# untitled.net
KiCad netlist of a schematic drawn in EAGLE
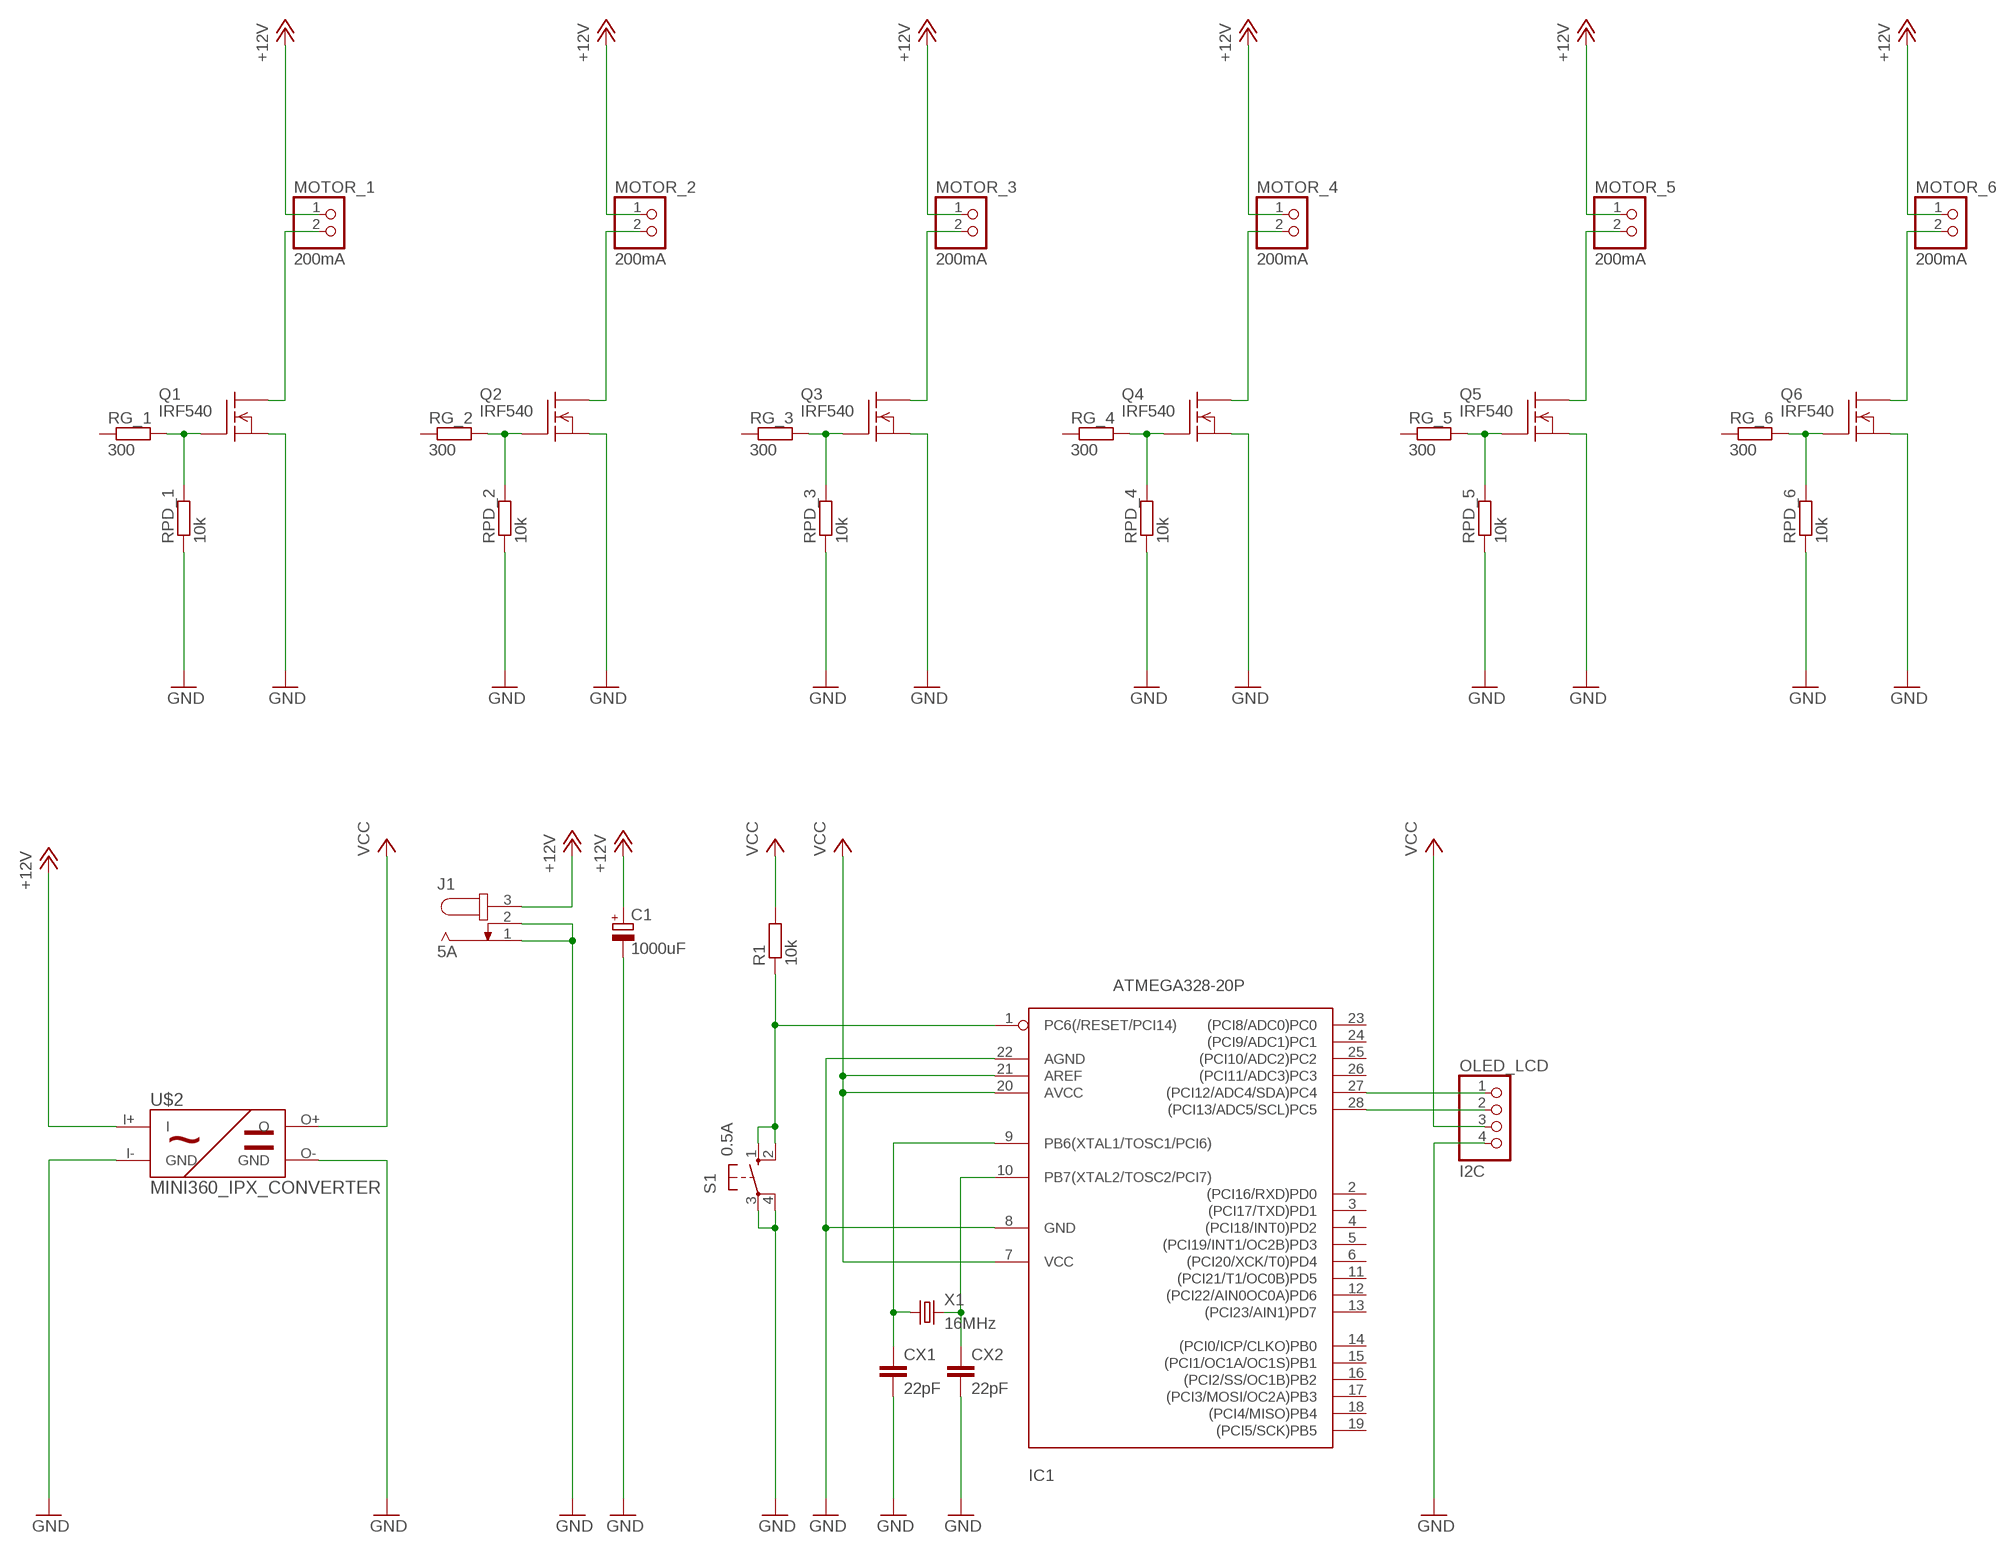
[diagram p0: schematic, sheet 1]

(export (version "E")
  (design (tool "Eeschema 10.0.6"))
  (components
    (comp (ref "C1")
      (value "1000uF")
      (footprint "eagle-import:E5-8,5")
      (libsource (lib "eagle-import") (part "CPOL-EUE5-8.5"))
    )
    (comp (ref "CX1")
      (value "22pF")
      (footprint "eagle-import:C050-025X075")
      (libsource (lib "eagle-import") (part "C-EU050-025X075"))
    )
    (comp (ref "CX2")
      (value "22pF")
      (footprint "eagle-import:C050-025X075")
      (libsource (lib "eagle-import") (part "C-EU050-025X075"))
    )
    (comp (ref "IC1")
      (value "ATMEGA328-20P")
      (footprint "eagle-import:DIL28-3")
      (libsource (lib "eagle-import") (part "ATMEGA328P-20"))
    )
    (comp (ref "J1")
      (value "5A")
      (footprint "eagle-import:SPC4078")
      (libsource (lib "eagle-import") (part "JACK-PLUG1"))
    )
    (comp (ref "MOTOR_1")
      (value "200mA")
      (footprint "eagle-import:1X02")
      (libsource (lib "eagle-import") (part "PINHD-1X2"))
    )
    (comp (ref "MOTOR_2")
      (value "200mA")
      (footprint "eagle-import:1X02")
      (libsource (lib "eagle-import") (part "PINHD-1X2"))
    )
    (comp (ref "MOTOR_3")
      (value "200mA")
      (footprint "eagle-import:1X02")
      (libsource (lib "eagle-import") (part "PINHD-1X2"))
    )
    (comp (ref "MOTOR_4")
      (value "200mA")
      (footprint "eagle-import:1X02")
      (libsource (lib "eagle-import") (part "PINHD-1X2"))
    )
    (comp (ref "MOTOR_5")
      (value "200mA")
      (footprint "eagle-import:1X02")
      (libsource (lib "eagle-import") (part "PINHD-1X2"))
    )
    (comp (ref "MOTOR_6")
      (value "200mA")
      (footprint "eagle-import:1X02")
      (libsource (lib "eagle-import") (part "PINHD-1X2"))
    )
    (comp (ref "OLED_LCD")
      (value "I2C")
      (footprint "eagle-import:1X04")
      (libsource (lib "eagle-import") (part "PINHD-1X4"))
    )
    (comp (ref "Q1")
      (value "IRF540")
      (footprint "eagle-import:TO220")
      (libsource (lib "eagle-import") (part "IRF540"))
    )
    (comp (ref "Q2")
      (value "IRF540")
      (footprint "eagle-import:TO220")
      (libsource (lib "eagle-import") (part "IRF540"))
    )
    (comp (ref "Q3")
      (value "IRF540")
      (footprint "eagle-import:TO220")
      (libsource (lib "eagle-import") (part "IRF540"))
    )
    (comp (ref "Q4")
      (value "IRF540")
      (footprint "eagle-import:TO220")
      (libsource (lib "eagle-import") (part "IRF540"))
    )
    (comp (ref "Q5")
      (value "IRF540")
      (footprint "eagle-import:TO220")
      (libsource (lib "eagle-import") (part "IRF540"))
    )
    (comp (ref "Q6")
      (value "IRF540")
      (footprint "eagle-import:TO220")
      (libsource (lib "eagle-import") (part "IRF540"))
    )
    (comp (ref "R1")
      (value "10k")
      (footprint "eagle-import:0207_10")
      (libsource (lib "eagle-import") (part "R-EU_0207/10"))
    )
    (comp (ref "RG_1")
      (value "300")
      (footprint "eagle-import:0207_10")
      (libsource (lib "eagle-import") (part "R-EU_0207/10"))
    )
    (comp (ref "RG_2")
      (value "300")
      (footprint "eagle-import:0207_10")
      (libsource (lib "eagle-import") (part "R-EU_0207/10"))
    )
    (comp (ref "RG_3")
      (value "300")
      (footprint "eagle-import:0207_10")
      (libsource (lib "eagle-import") (part "R-EU_0207/10"))
    )
    (comp (ref "RG_4")
      (value "300")
      (footprint "eagle-import:0207_10")
      (libsource (lib "eagle-import") (part "R-EU_0207/10"))
    )
    (comp (ref "RG_5")
      (value "300")
      (footprint "eagle-import:0207_10")
      (libsource (lib "eagle-import") (part "R-EU_0207/10"))
    )
    (comp (ref "RG_6")
      (value "300")
      (footprint "eagle-import:0207_10")
      (libsource (lib "eagle-import") (part "R-EU_0207/10"))
    )
    (comp (ref "RPD_1")
      (value "10k")
      (footprint "eagle-import:0207_10")
      (libsource (lib "eagle-import") (part "R-EU_0207/10"))
    )
    (comp (ref "RPD_2")
      (value "10k")
      (footprint "eagle-import:0207_10")
      (libsource (lib "eagle-import") (part "R-EU_0207/10"))
    )
    (comp (ref "RPD_3")
      (value "10k")
      (footprint "eagle-import:0207_10")
      (libsource (lib "eagle-import") (part "R-EU_0207/10"))
    )
    (comp (ref "RPD_4")
      (value "10k")
      (footprint "eagle-import:0207_10")
      (libsource (lib "eagle-import") (part "R-EU_0207/10"))
    )
    (comp (ref "RPD_5")
      (value "10k")
      (footprint "eagle-import:0207_10")
      (libsource (lib "eagle-import") (part "R-EU_0207/10"))
    )
    (comp (ref "RPD_6")
      (value "10k")
      (footprint "eagle-import:0207_10")
      (libsource (lib "eagle-import") (part "R-EU_0207/10"))
    )
    (comp (ref "S1")
      (value "0.5A")
      (footprint "eagle-import:B3F-10XX")
      (fields (field (name "MPN") "B3F-1000"))
      (libsource (lib "eagle-import") (part "10-XX"))
    )
    (comp (ref "U$2")
      (value "MINI360_IPX_CONVERTER")
      (footprint "eagle-import:MINI360_IPX_CONVERTER")
      (libsource (lib "eagle-import") (part "MINI360_IPX_CONVERTER"))
    )
    (comp (ref "X1")
      (value "16MHz")
      (footprint "eagle-import:HC49_S")
      (libsource (lib "eagle-import") (part "CRYSTALHC49S"))
    )
  )
  (nets
    (net (code "1") (name "+12V") (class "Default")
      (node (ref "C1") (pin "+") (pinfunction "+_+") (pintype "passive"))
      (node (ref "J1") (pin "3") (pinfunction "3_3") (pintype "passive"))
      (node (ref "MOTOR_1") (pin "1") (pinfunction "1_1") (pintype "passive"))
      (node (ref "MOTOR_2") (pin "1") (pinfunction "1_1") (pintype "passive"))
      (node (ref "MOTOR_3") (pin "1") (pinfunction "1_1") (pintype "passive"))
      (node (ref "MOTOR_4") (pin "1") (pinfunction "1_1") (pintype "passive"))
      (node (ref "MOTOR_5") (pin "1") (pinfunction "1_1") (pintype "passive"))
      (node (ref "MOTOR_6") (pin "1") (pinfunction "1_1") (pintype "passive"))
      (node (ref "U$2") (pin "I+") (pinfunction "I_I+") (pintype "bidirectional"))
    )
    (net (code "2") (name "GND") (class "Default")
      (node (ref "C1") (pin "-") (pinfunction "-_-") (pintype "passive"))
      (node (ref "CX1") (pin "2") (pinfunction "2_2") (pintype "passive"))
      (node (ref "CX2") (pin "2") (pinfunction "2_2") (pintype "passive"))
      (node (ref "IC1") (pin "22") (pinfunction "AGND_22") (pintype "bidirectional"))
      (node (ref "IC1") (pin "8") (pinfunction "GND_8") (pintype "bidirectional"))
      (node (ref "J1") (pin "1") (pinfunction "1_1") (pintype "passive"))
      (node (ref "J1") (pin "2") (pinfunction "2_2") (pintype "passive"))
      (node (ref "OLED_LCD") (pin "4") (pinfunction "4_4") (pintype "passive"))
      (node (ref "Q1") (pin "3") (pinfunction "S_3") (pintype "passive"))
      (node (ref "Q2") (pin "3") (pinfunction "S_3") (pintype "passive"))
      (node (ref "Q3") (pin "3") (pinfunction "S_3") (pintype "passive"))
      (node (ref "Q4") (pin "3") (pinfunction "S_3") (pintype "passive"))
      (node (ref "Q5") (pin "3") (pinfunction "S_3") (pintype "passive"))
      (node (ref "Q6") (pin "3") (pinfunction "S_3") (pintype "passive"))
      (node (ref "RPD_1") (pin "1") (pinfunction "1_1") (pintype "passive"))
      (node (ref "RPD_2") (pin "1") (pinfunction "1_1") (pintype "passive"))
      (node (ref "RPD_3") (pin "1") (pinfunction "1_1") (pintype "passive"))
      (node (ref "RPD_4") (pin "1") (pinfunction "1_1") (pintype "passive"))
      (node (ref "RPD_5") (pin "1") (pinfunction "1_1") (pintype "passive"))
      (node (ref "RPD_6") (pin "1") (pinfunction "1_1") (pintype "passive"))
      (node (ref "S1") (pin "3") (pinfunction "P_3") (pintype "passive"))
      (node (ref "S1") (pin "4") (pinfunction "P1_4") (pintype "passive"))
      (node (ref "U$2") (pin "I-") (pinfunction "GND_I-") (pintype "bidirectional"))
      (node (ref "U$2") (pin "O-") (pinfunction "GND_O-") (pintype "bidirectional"))
    )
    (net (code "3") (name "Net-(IC1-(PCI12{slash}ADC4{slash}SDA)PC4)") (class "Default")
      (node (ref "IC1") (pin "27") (pinfunction "(PCI12/ADC4/SDA)PC4_27") (pintype "bidirectional"))
      (node (ref "OLED_LCD") (pin "1") (pinfunction "1_1") (pintype "passive"))
    )
    (net (code "4") (name "Net-(IC1-(PCI13{slash}ADC5{slash}SCL)PC5)") (class "Default")
      (node (ref "IC1") (pin "28") (pinfunction "(PCI13/ADC5/SCL)PC5_28") (pintype "bidirectional"))
      (node (ref "OLED_LCD") (pin "2") (pinfunction "2_2") (pintype "passive"))
    )
    (net (code "5") (name "Net-(IC1-PB6(XTAL1{slash}TOSC1{slash}PCI6))") (class "Default")
      (node (ref "CX1") (pin "1") (pinfunction "1_1") (pintype "passive"))
      (node (ref "IC1") (pin "9") (pinfunction "PB6(XTAL1/TOSC1/PCI6)_9") (pintype "bidirectional"))
      (node (ref "X1") (pin "1") (pinfunction "1_1") (pintype "passive"))
    )
    (net (code "6") (name "Net-(IC1-PB7(XTAL2{slash}TOSC2{slash}PCI7))") (class "Default")
      (node (ref "CX2") (pin "1") (pinfunction "1_1") (pintype "passive"))
      (node (ref "IC1") (pin "10") (pinfunction "PB7(XTAL2/TOSC2/PCI7)_10") (pintype "bidirectional"))
      (node (ref "X1") (pin "2") (pinfunction "2_2") (pintype "passive"))
    )
    (net (code "7") (name "Net-(IC1-PC6({slash}RESET{slash}PCI14))") (class "Default")
      (node (ref "IC1") (pin "1") (pinfunction "PC6(/RESET/PCI14)_1") (pintype "bidirectional"))
      (node (ref "R1") (pin "1") (pinfunction "1_1") (pintype "passive"))
      (node (ref "S1") (pin "1") (pinfunction "S_1") (pintype "passive"))
      (node (ref "S1") (pin "2") (pinfunction "S1_2") (pintype "passive"))
    )
    (net (code "8") (name "Net-(Q1-D)") (class "Default")
      (node (ref "MOTOR_1") (pin "2") (pinfunction "2_2") (pintype "passive"))
      (node (ref "Q1") (pin "2") (pinfunction "D_2") (pintype "passive"))
    )
    (net (code "9") (name "Net-(Q1-G)") (class "Default")
      (node (ref "Q1") (pin "1") (pinfunction "G_1") (pintype "passive"))
      (node (ref "RG_1") (pin "2") (pinfunction "2_2") (pintype "passive"))
      (node (ref "RPD_1") (pin "2") (pinfunction "2_2") (pintype "passive"))
    )
    (net (code "10") (name "Net-(Q2-D)") (class "Default")
      (node (ref "MOTOR_2") (pin "2") (pinfunction "2_2") (pintype "passive"))
      (node (ref "Q2") (pin "2") (pinfunction "D_2") (pintype "passive"))
    )
    (net (code "11") (name "Net-(Q2-G)") (class "Default")
      (node (ref "Q2") (pin "1") (pinfunction "G_1") (pintype "passive"))
      (node (ref "RG_2") (pin "2") (pinfunction "2_2") (pintype "passive"))
      (node (ref "RPD_2") (pin "2") (pinfunction "2_2") (pintype "passive"))
    )
    (net (code "12") (name "Net-(Q3-D)") (class "Default")
      (node (ref "MOTOR_3") (pin "2") (pinfunction "2_2") (pintype "passive"))
      (node (ref "Q3") (pin "2") (pinfunction "D_2") (pintype "passive"))
    )
    (net (code "13") (name "Net-(Q3-G)") (class "Default")
      (node (ref "Q3") (pin "1") (pinfunction "G_1") (pintype "passive"))
      (node (ref "RG_3") (pin "2") (pinfunction "2_2") (pintype "passive"))
      (node (ref "RPD_3") (pin "2") (pinfunction "2_2") (pintype "passive"))
    )
    (net (code "14") (name "Net-(Q4-D)") (class "Default")
      (node (ref "MOTOR_4") (pin "2") (pinfunction "2_2") (pintype "passive"))
      (node (ref "Q4") (pin "2") (pinfunction "D_2") (pintype "passive"))
    )
    (net (code "15") (name "Net-(Q4-G)") (class "Default")
      (node (ref "Q4") (pin "1") (pinfunction "G_1") (pintype "passive"))
      (node (ref "RG_4") (pin "2") (pinfunction "2_2") (pintype "passive"))
      (node (ref "RPD_4") (pin "2") (pinfunction "2_2") (pintype "passive"))
    )
    (net (code "16") (name "Net-(Q5-D)") (class "Default")
      (node (ref "MOTOR_5") (pin "2") (pinfunction "2_2") (pintype "passive"))
      (node (ref "Q5") (pin "2") (pinfunction "D_2") (pintype "passive"))
    )
    (net (code "17") (name "Net-(Q5-G)") (class "Default")
      (node (ref "Q5") (pin "1") (pinfunction "G_1") (pintype "passive"))
      (node (ref "RG_5") (pin "2") (pinfunction "2_2") (pintype "passive"))
      (node (ref "RPD_5") (pin "2") (pinfunction "2_2") (pintype "passive"))
    )
    (net (code "18") (name "Net-(Q6-D)") (class "Default")
      (node (ref "MOTOR_6") (pin "2") (pinfunction "2_2") (pintype "passive"))
      (node (ref "Q6") (pin "2") (pinfunction "D_2") (pintype "passive"))
    )
    (net (code "19") (name "Net-(Q6-G)") (class "Default")
      (node (ref "Q6") (pin "1") (pinfunction "G_1") (pintype "passive"))
      (node (ref "RG_6") (pin "2") (pinfunction "2_2") (pintype "passive"))
      (node (ref "RPD_6") (pin "2") (pinfunction "2_2") (pintype "passive"))
    )
    (net (code "20") (name "VCC") (class "Default")
      (node (ref "IC1") (pin "20") (pinfunction "AVCC_20") (pintype "bidirectional"))
      (node (ref "IC1") (pin "21") (pinfunction "AREF_21") (pintype "bidirectional"))
      (node (ref "IC1") (pin "7") (pinfunction "VCC_7") (pintype "bidirectional"))
      (node (ref "OLED_LCD") (pin "3") (pinfunction "3_3") (pintype "passive"))
      (node (ref "R1") (pin "2") (pinfunction "2_2") (pintype "passive"))
      (node (ref "U$2") (pin "O+") (pinfunction "O_O+") (pintype "bidirectional"))
    )
    (net (code "21") (name "unconnected-(IC1-(PCI0{slash}ICP{slash}CLKO)PB0-Pad14)") (class "Default")
      (node (ref "IC1") (pin "14") (pinfunction "(PCI0/ICP/CLKO)PB0_14") (pintype "bidirectional"))
    )
    (net (code "22") (name "unconnected-(IC1-(PCI1{slash}OC1A{slash}OC1S)PB1-Pad15)") (class "Default")
      (node (ref "IC1") (pin "15") (pinfunction "(PCI1/OC1A/OC1S)PB1_15") (pintype "bidirectional"))
    )
    (net (code "23") (name "unconnected-(IC1-(PCI2{slash}SS{slash}OC1B)PB2-Pad16)") (class "Default")
      (node (ref "IC1") (pin "16") (pinfunction "(PCI2/SS/OC1B)PB2_16") (pintype "bidirectional"))
    )
    (net (code "24") (name "unconnected-(IC1-(PCI3{slash}MOSI{slash}OC2A)PB3-Pad17)") (class "Default")
      (node (ref "IC1") (pin "17") (pinfunction "(PCI3/MOSI/OC2A)PB3_17") (pintype "bidirectional"))
    )
    (net (code "25") (name "unconnected-(IC1-(PCI4{slash}MISO)PB4-Pad18)") (class "Default")
      (node (ref "IC1") (pin "18") (pinfunction "(PCI4/MISO)PB4_18") (pintype "bidirectional"))
    )
    (net (code "26") (name "unconnected-(IC1-(PCI5{slash}SCK)PB5-Pad19)") (class "Default")
      (node (ref "IC1") (pin "19") (pinfunction "(PCI5/SCK)PB5_19") (pintype "bidirectional"))
    )
    (net (code "27") (name "unconnected-(IC1-(PCI8{slash}ADC0)PC0-Pad23)") (class "Default")
      (node (ref "IC1") (pin "23") (pinfunction "(PCI8/ADC0)PC0_23") (pintype "bidirectional"))
    )
    (net (code "28") (name "unconnected-(IC1-(PCI9{slash}ADC1)PC1-Pad24)") (class "Default")
      (node (ref "IC1") (pin "24") (pinfunction "(PCI9/ADC1)PC1_24") (pintype "bidirectional"))
    )
    (net (code "29") (name "unconnected-(IC1-(PCI10{slash}ADC2)PC2-Pad25)") (class "Default")
      (node (ref "IC1") (pin "25") (pinfunction "(PCI10/ADC2)PC2_25") (pintype "bidirectional"))
    )
    (net (code "30") (name "unconnected-(IC1-(PCI11{slash}ADC3)PC3-Pad26)") (class "Default")
      (node (ref "IC1") (pin "26") (pinfunction "(PCI11/ADC3)PC3_26") (pintype "bidirectional"))
    )
    (net (code "31") (name "unconnected-(IC1-(PCI16{slash}RXD)PD0-Pad2)") (class "Default")
      (node (ref "IC1") (pin "2") (pinfunction "(PCI16/RXD)PD0_2") (pintype "bidirectional"))
    )
    (net (code "32") (name "unconnected-(IC1-(PCI17{slash}TXD)PD1-Pad3)") (class "Default")
      (node (ref "IC1") (pin "3") (pinfunction "(PCI17/TXD)PD1_3") (pintype "bidirectional"))
    )
    (net (code "33") (name "unconnected-(IC1-(PCI18{slash}INT0)PD2-Pad4)") (class "Default")
      (node (ref "IC1") (pin "4") (pinfunction "(PCI18/INT0)PD2_4") (pintype "bidirectional"))
    )
    (net (code "34") (name "unconnected-(IC1-(PCI19{slash}INT1{slash}OC2B)PD3-Pad5)") (class "Default")
      (node (ref "IC1") (pin "5") (pinfunction "(PCI19/INT1/OC2B)PD3_5") (pintype "bidirectional"))
    )
    (net (code "35") (name "unconnected-(IC1-(PCI20{slash}XCK{slash}T0)PD4-Pad6)") (class "Default")
      (node (ref "IC1") (pin "6") (pinfunction "(PCI20/XCK/T0)PD4_6") (pintype "bidirectional"))
    )
    (net (code "36") (name "unconnected-(IC1-(PCI21{slash}T1{slash}OC0B)PD5-Pad11)") (class "Default")
      (node (ref "IC1") (pin "11") (pinfunction "(PCI21/T1/OC0B)PD5_11") (pintype "bidirectional"))
    )
    (net (code "37") (name "unconnected-(IC1-(PCI22{slash}AIN0OC0A)PD6-Pad12)") (class "Default")
      (node (ref "IC1") (pin "12") (pinfunction "(PCI22/AIN0OC0A)PD6_12") (pintype "bidirectional"))
    )
    (net (code "38") (name "unconnected-(IC1-(PCI23{slash}AIN1)PD7-Pad13)") (class "Default")
      (node (ref "IC1") (pin "13") (pinfunction "(PCI23/AIN1)PD7_13") (pintype "bidirectional"))
    )
    (net (code "39") (name "unconnected-(RG_1-Pad1)") (class "Default")
      (node (ref "RG_1") (pin "1") (pinfunction "1_1") (pintype "passive"))
    )
    (net (code "40") (name "unconnected-(RG_2-Pad1)") (class "Default")
      (node (ref "RG_2") (pin "1") (pinfunction "1_1") (pintype "passive"))
    )
    (net (code "41") (name "unconnected-(RG_3-Pad1)") (class "Default")
      (node (ref "RG_3") (pin "1") (pinfunction "1_1") (pintype "passive"))
    )
    (net (code "42") (name "unconnected-(RG_4-Pad1)") (class "Default")
      (node (ref "RG_4") (pin "1") (pinfunction "1_1") (pintype "passive"))
    )
    (net (code "43") (name "unconnected-(RG_5-Pad1)") (class "Default")
      (node (ref "RG_5") (pin "1") (pinfunction "1_1") (pintype "passive"))
    )
    (net (code "44") (name "unconnected-(RG_6-Pad1)") (class "Default")
      (node (ref "RG_6") (pin "1") (pinfunction "1_1") (pintype "passive"))
    )
  )
)
